# clock.net
KiCad netlist of a schematic drawn in Altium Designer
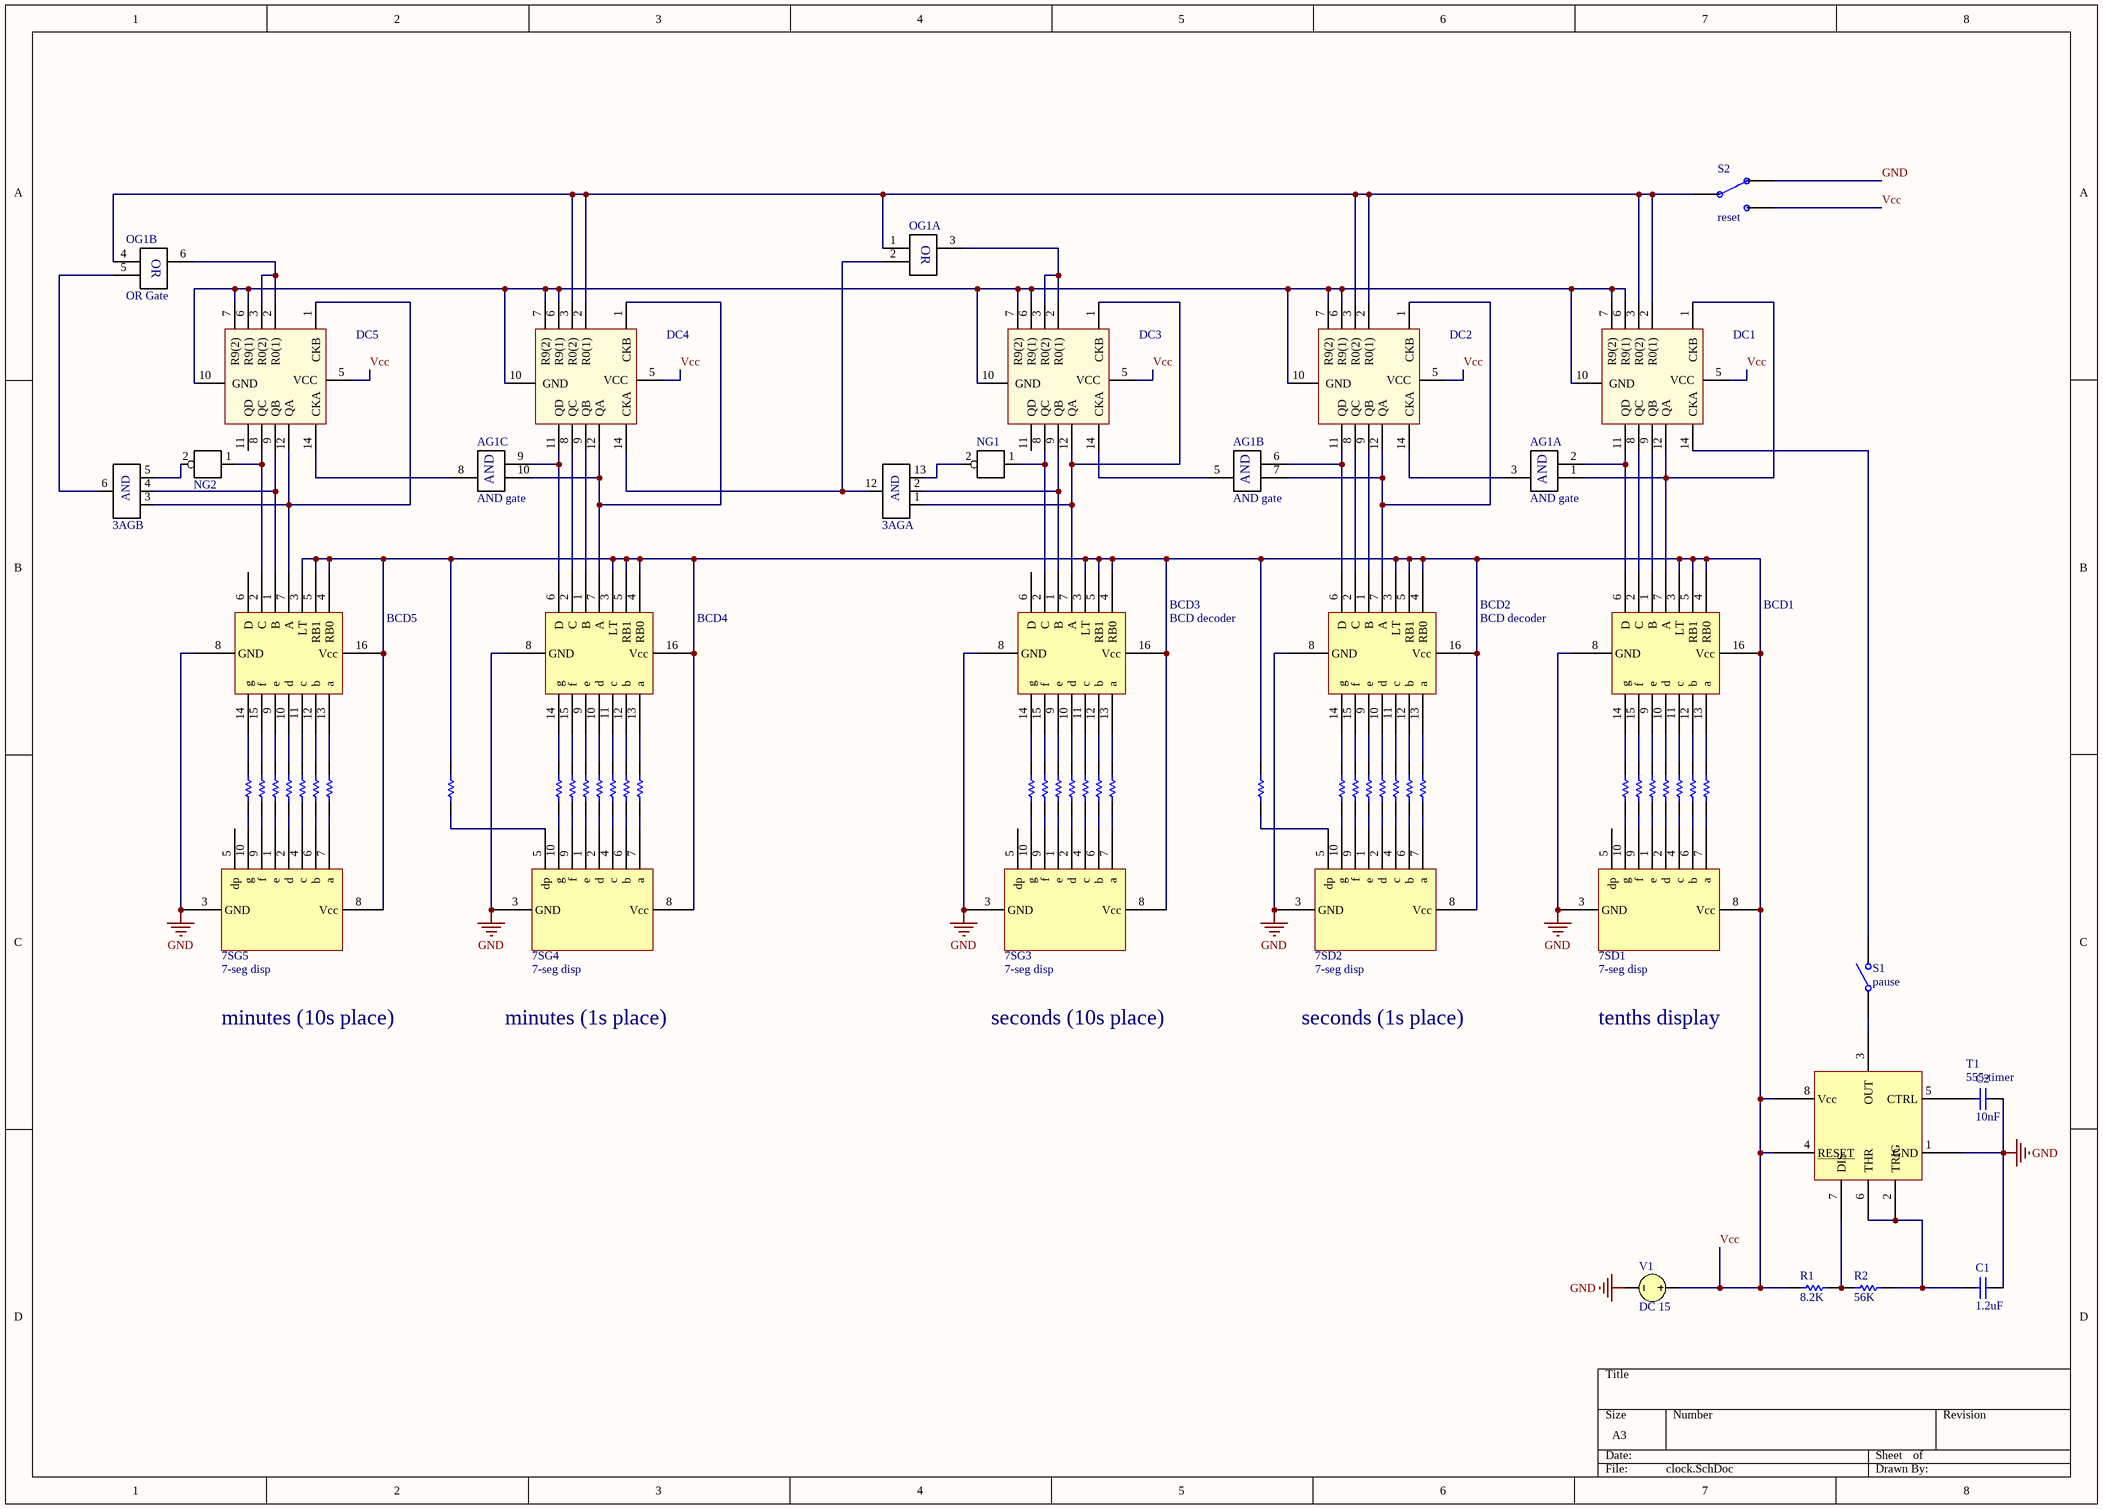
[diagram p0: clock.SchDoc]

(export (version "E")
  (design (tool "Eeschema 10.0.6"))
  (components
    (comp (ref "3AG") (value "DM7411N") (libsource (lib "clockproject") (part "3AND gate")))
    (comp (ref "7SD1") (value "7-seg disp") (libsource (lib "clockproject") (part "7-seg disp")))
    (comp (ref "7SD2") (value "7-seg disp") (libsource (lib "clockproject") (part "7-seg disp")))
    (comp (ref "7SG3") (value "7-seg disp") (libsource (lib "clockproject") (part "7-seg disp")))
    (comp (ref "7SG4") (value "7-seg disp") (libsource (lib "clockproject") (part "7-seg disp")))
    (comp (ref "7SG5") (value "7-seg disp") (libsource (lib "clockproject") (part "7-seg disp")))
    (comp (ref "AG1") (value "AND gate") (libsource (lib "clockproject") (part "AND gate")))
    (comp (ref "BCD1") (value "BCD decoder") (libsource (lib "clockproject") (part "BCD decoder")))
    (comp (ref "BCD2") (value "BCD decoder") (libsource (lib "clockproject") (part "BCD decoder")))
    (comp (ref "BCD3") (value "BCD decoder") (libsource (lib "clockproject") (part "BCD decoder")))
    (comp (ref "BCD4") (value "BCD decoder") (libsource (lib "clockproject") (part "BCD decoder")))
    (comp (ref "BCD5") (value "BCD decoder") (libsource (lib "clockproject") (part "BCD decoder")))
    (comp (ref "C1")
      (value "1.2uF")
      (footprint "RAD-0.3")
      (description "Capacitor")
      (fields (field (name "Comment") "Cap") (field (name "PUBLISHER") "Altium Limited"))
      (libsource (lib "Miscellaneous Devices") (part "Cap"))
    )
    (comp (ref "C2")
      (value "10nF")
      (footprint "RAD-0.3")
      (description "Capacitor")
      (fields (field (name "Comment") "Cap") (field (name "PUBLISHER") "Altium Limited"))
      (libsource (lib "Miscellaneous Devices") (part "Cap"))
    )
    (comp (ref "DC1")
      (value "Decade counter (SN76LS90N)")
      (footprint "SN74LS90N")
      (libsource (lib "clockproject") (part "Decade counter (SN76LS90N)"))
    )
    (comp (ref "DC2")
      (value "Decade counter (SN76LS90N)")
      (footprint "SN74LS90N")
      (libsource (lib "clockproject") (part "Decade counter (SN76LS90N)"))
    )
    (comp (ref "DC3")
      (value "Decade counter (SN76LS90N)")
      (footprint "SN74LS90N")
      (libsource (lib "clockproject") (part "Decade counter (SN76LS90N)"))
    )
    (comp (ref "DC4")
      (value "Decade counter (SN76LS90N)")
      (footprint "SN74LS90N")
      (libsource (lib "clockproject") (part "Decade counter (SN76LS90N)"))
    )
    (comp (ref "DC5")
      (value "Decade counter (SN76LS90N)")
      (footprint "SN74LS90N")
      (libsource (lib "clockproject") (part "Decade counter (SN76LS90N)"))
    )
    (comp (ref "NG1") (value "NOT gate") (libsource (lib "clockproject") (part "NOT gate")))
    (comp (ref "NG2") (value "NOT gate") (libsource (lib "clockproject") (part "NOT gate")))
    (comp (ref "OG1") (value "OR Gate") (libsource (lib "clockproject") (part "OR Gate")))
    (comp (ref "R1")
      (value "8.2K")
      (footprint "AXIAL-0.3")
      (description "Resistor")
      (fields (field (name "Comment") "Res1") (field (name "PUBLISHER") "Altium Limited"))
      (libsource (lib "Miscellaneous Devices") (part "Res1"))
    )
    (comp (ref "R2")
      (value "56K")
      (footprint "AXIAL-0.3")
      (description "Resistor")
      (fields (field (name "Comment") "Res1") (field (name "PUBLISHER") "Altium Limited"))
      (libsource (lib "Miscellaneous Devices") (part "Res1"))
    )
    (comp (ref "R3")
      (value "Res1")
      (footprint "AXIAL-0.3")
      (description "Resistor")
      (fields (field (name "PUBLISHER") "Altium Limited"))
      (libsource (lib "Miscellaneous Devices") (part "Res1"))
    )
    (comp (ref "R4")
      (value "Res1")
      (footprint "AXIAL-0.3")
      (description "Resistor")
      (fields (field (name "PUBLISHER") "Altium Limited"))
      (libsource (lib "Miscellaneous Devices") (part "Res1"))
    )
    (comp (ref "R5")
      (value "Res1")
      (footprint "AXIAL-0.3")
      (description "Resistor")
      (fields (field (name "PUBLISHER") "Altium Limited"))
      (libsource (lib "Miscellaneous Devices") (part "Res1"))
    )
    (comp (ref "R6")
      (value "Res1")
      (footprint "AXIAL-0.3")
      (description "Resistor")
      (fields (field (name "PUBLISHER") "Altium Limited"))
      (libsource (lib "Miscellaneous Devices") (part "Res1"))
    )
    (comp (ref "R7")
      (value "Res1")
      (footprint "AXIAL-0.3")
      (description "Resistor")
      (fields (field (name "PUBLISHER") "Altium Limited"))
      (libsource (lib "Miscellaneous Devices") (part "Res1"))
    )
    (comp (ref "R8")
      (value "Res1")
      (footprint "AXIAL-0.3")
      (description "Resistor")
      (fields (field (name "PUBLISHER") "Altium Limited"))
      (libsource (lib "Miscellaneous Devices") (part "Res1"))
    )
    (comp (ref "R9")
      (value "Res1")
      (footprint "AXIAL-0.3")
      (description "Resistor")
      (fields (field (name "PUBLISHER") "Altium Limited"))
      (libsource (lib "Miscellaneous Devices") (part "Res1"))
    )
    (comp (ref "R10")
      (value "Res1")
      (footprint "AXIAL-0.3")
      (description "Resistor")
      (fields (field (name "PUBLISHER") "Altium Limited"))
      (libsource (lib "Miscellaneous Devices") (part "Res1"))
    )
    (comp (ref "R11")
      (value "Res1")
      (footprint "AXIAL-0.3")
      (description "Resistor")
      (fields (field (name "PUBLISHER") "Altium Limited"))
      (libsource (lib "Miscellaneous Devices") (part "Res1"))
    )
    (comp (ref "R12")
      (value "Res1")
      (footprint "AXIAL-0.3")
      (description "Resistor")
      (fields (field (name "PUBLISHER") "Altium Limited"))
      (libsource (lib "Miscellaneous Devices") (part "Res1"))
    )
    (comp (ref "R13")
      (value "Res1")
      (footprint "AXIAL-0.3")
      (description "Resistor")
      (fields (field (name "PUBLISHER") "Altium Limited"))
      (libsource (lib "Miscellaneous Devices") (part "Res1"))
    )
    (comp (ref "R14")
      (value "Res1")
      (footprint "AXIAL-0.3")
      (description "Resistor")
      (fields (field (name "PUBLISHER") "Altium Limited"))
      (libsource (lib "Miscellaneous Devices") (part "Res1"))
    )
    (comp (ref "R15")
      (value "Res1")
      (footprint "AXIAL-0.3")
      (description "Resistor")
      (fields (field (name "PUBLISHER") "Altium Limited"))
      (libsource (lib "Miscellaneous Devices") (part "Res1"))
    )
    (comp (ref "R16")
      (value "Res1")
      (footprint "AXIAL-0.3")
      (description "Resistor")
      (fields (field (name "PUBLISHER") "Altium Limited"))
      (libsource (lib "Miscellaneous Devices") (part "Res1"))
    )
    (comp (ref "R17")
      (value "Res1")
      (footprint "AXIAL-0.3")
      (description "Resistor")
      (fields (field (name "PUBLISHER") "Altium Limited"))
      (libsource (lib "Miscellaneous Devices") (part "Res1"))
    )
    (comp (ref "R18")
      (value "Res1")
      (footprint "AXIAL-0.3")
      (description "Resistor")
      (fields (field (name "PUBLISHER") "Altium Limited"))
      (libsource (lib "Miscellaneous Devices") (part "Res1"))
    )
    (comp (ref "R19")
      (value "Res1")
      (footprint "AXIAL-0.3")
      (description "Resistor")
      (fields (field (name "PUBLISHER") "Altium Limited"))
      (libsource (lib "Miscellaneous Devices") (part "Res1"))
    )
    (comp (ref "R20")
      (value "Res1")
      (footprint "AXIAL-0.3")
      (description "Resistor")
      (fields (field (name "PUBLISHER") "Altium Limited"))
      (libsource (lib "Miscellaneous Devices") (part "Res1"))
    )
    (comp (ref "R21")
      (value "Res1")
      (footprint "AXIAL-0.3")
      (description "Resistor")
      (fields (field (name "PUBLISHER") "Altium Limited"))
      (libsource (lib "Miscellaneous Devices") (part "Res1"))
    )
    (comp (ref "R22")
      (value "Res1")
      (footprint "AXIAL-0.3")
      (description "Resistor")
      (fields (field (name "PUBLISHER") "Altium Limited"))
      (libsource (lib "Miscellaneous Devices") (part "Res1"))
    )
    (comp (ref "R23")
      (value "Res1")
      (footprint "AXIAL-0.3")
      (description "Resistor")
      (fields (field (name "PUBLISHER") "Altium Limited"))
      (libsource (lib "Miscellaneous Devices") (part "Res1"))
    )
    (comp (ref "R24")
      (value "Res1")
      (footprint "AXIAL-0.3")
      (description "Resistor")
      (fields (field (name "PUBLISHER") "Altium Limited"))
      (libsource (lib "Miscellaneous Devices") (part "Res1"))
    )
    (comp (ref "R25")
      (value "Res1")
      (footprint "AXIAL-0.3")
      (description "Resistor")
      (fields (field (name "PUBLISHER") "Altium Limited"))
      (libsource (lib "Miscellaneous Devices") (part "Res1"))
    )
    (comp (ref "R26")
      (value "Res1")
      (footprint "AXIAL-0.3")
      (description "Resistor")
      (fields (field (name "PUBLISHER") "Altium Limited"))
      (libsource (lib "Miscellaneous Devices") (part "Res1"))
    )
    (comp (ref "R27")
      (value "Res1")
      (footprint "AXIAL-0.3")
      (description "Resistor")
      (fields (field (name "PUBLISHER") "Altium Limited"))
      (libsource (lib "Miscellaneous Devices") (part "Res1"))
    )
    (comp (ref "R28")
      (value "Res1")
      (footprint "AXIAL-0.3")
      (description "Resistor")
      (fields (field (name "PUBLISHER") "Altium Limited"))
      (libsource (lib "Miscellaneous Devices") (part "Res1"))
    )
    (comp (ref "R29")
      (value "Res1")
      (footprint "AXIAL-0.3")
      (description "Resistor")
      (fields (field (name "PUBLISHER") "Altium Limited"))
      (libsource (lib "Miscellaneous Devices") (part "Res1"))
    )
    (comp (ref "R30")
      (value "Res1")
      (footprint "AXIAL-0.3")
      (description "Resistor")
      (fields (field (name "PUBLISHER") "Altium Limited"))
      (libsource (lib "Miscellaneous Devices") (part "Res1"))
    )
    (comp (ref "R31")
      (value "Res1")
      (footprint "AXIAL-0.3")
      (description "Resistor")
      (fields (field (name "PUBLISHER") "Altium Limited"))
      (libsource (lib "Miscellaneous Devices") (part "Res1"))
    )
    (comp (ref "R32")
      (value "Res1")
      (footprint "AXIAL-0.3")
      (description "Resistor")
      (fields (field (name "PUBLISHER") "Altium Limited"))
      (libsource (lib "Miscellaneous Devices") (part "Res1"))
    )
    (comp (ref "R33")
      (value "Res1")
      (footprint "AXIAL-0.3")
      (description "Resistor")
      (fields (field (name "PUBLISHER") "Altium Limited"))
      (libsource (lib "Miscellaneous Devices") (part "Res1"))
    )
    (comp (ref "R34")
      (value "Res1")
      (footprint "AXIAL-0.3")
      (description "Resistor")
      (fields (field (name "PUBLISHER") "Altium Limited"))
      (libsource (lib "Miscellaneous Devices") (part "Res1"))
    )
    (comp (ref "R35")
      (value "Res1")
      (footprint "AXIAL-0.3")
      (description "Resistor")
      (fields (field (name "PUBLISHER") "Altium Limited"))
      (libsource (lib "Miscellaneous Devices") (part "Res1"))
    )
    (comp (ref "R36")
      (value "Res1")
      (footprint "AXIAL-0.3")
      (description "Resistor")
      (fields (field (name "PUBLISHER") "Altium Limited"))
      (libsource (lib "Miscellaneous Devices") (part "Res1"))
    )
    (comp (ref "R37")
      (value "Res1")
      (footprint "AXIAL-0.3")
      (description "Resistor")
      (fields (field (name "PUBLISHER") "Altium Limited"))
      (libsource (lib "Miscellaneous Devices") (part "Res1"))
    )
    (comp (ref "R38")
      (value "Res1")
      (footprint "AXIAL-0.3")
      (description "Resistor")
      (fields (field (name "PUBLISHER") "Altium Limited"))
      (libsource (lib "Miscellaneous Devices") (part "Res1"))
    )
    (comp (ref "R39")
      (value "Res1")
      (footprint "AXIAL-0.3")
      (description "Resistor")
      (fields (field (name "PUBLISHER") "Altium Limited"))
      (libsource (lib "Miscellaneous Devices") (part "Res1"))
    )
    (comp (ref "S1")
      (value "pause")
      (footprint "SPST-2")
      (description "Single-Pole, Single-Throw Switch")
      (fields (field (name "PUBLISHER") "Altium Limited"))
      (libsource (lib "Miscellaneous Devices") (part "SW-SPST"))
    )
    (comp (ref "S2") (value "reset") (footprint "Switch") (libsource (lib "clockproject") (part "Switch")))
    (comp (ref "T1") (value "555-timer") (libsource (lib "clockproject") (part "555-timer")))
    (comp (ref "V1")
      (value "DC 15")
      (description "Voltage Source")
      (fields (field (name "PUBLISHER") "Altium Limited"))
      (libsource (lib "Simulation Generic Components") (part "VSRC"))
    )
  )
  (nets
    (net (code "1") (name "/Vcc") (class "Default")
      (node (ref "7SD1") (pin "8") (pinfunction "Vcc_8") (pintype "passive"))
      (node (ref "7SD2") (pin "8") (pinfunction "Vcc_8") (pintype "passive"))
      (node (ref "7SG3") (pin "8") (pinfunction "Vcc_8") (pintype "passive"))
      (node (ref "7SG4") (pin "8") (pinfunction "Vcc_8") (pintype "passive"))
      (node (ref "7SG5") (pin "8") (pinfunction "Vcc_8") (pintype "passive"))
      (node (ref "BCD1") (pin "16") (pinfunction "Vcc_16") (pintype "passive"))
      (node (ref "BCD1") (pin "3") (pinfunction "LT_3") (pintype "passive"))
      (node (ref "BCD1") (pin "4") (pinfunction "RB0_4") (pintype "passive"))
      (node (ref "BCD1") (pin "5") (pinfunction "RB1_5") (pintype "passive"))
      (node (ref "BCD2") (pin "16") (pinfunction "Vcc_16") (pintype "passive"))
      (node (ref "BCD2") (pin "3") (pinfunction "LT_3") (pintype "passive"))
      (node (ref "BCD2") (pin "4") (pinfunction "RB0_4") (pintype "passive"))
      (node (ref "BCD2") (pin "5") (pinfunction "RB1_5") (pintype "passive"))
      (node (ref "BCD3") (pin "16") (pinfunction "Vcc_16") (pintype "passive"))
      (node (ref "BCD3") (pin "3") (pinfunction "LT_3") (pintype "passive"))
      (node (ref "BCD3") (pin "4") (pinfunction "RB0_4") (pintype "passive"))
      (node (ref "BCD3") (pin "5") (pinfunction "RB1_5") (pintype "passive"))
      (node (ref "BCD4") (pin "16") (pinfunction "Vcc_16") (pintype "passive"))
      (node (ref "BCD4") (pin "3") (pinfunction "LT_3") (pintype "passive"))
      (node (ref "BCD4") (pin "4") (pinfunction "RB0_4") (pintype "passive"))
      (node (ref "BCD4") (pin "5") (pinfunction "RB1_5") (pintype "passive"))
      (node (ref "BCD5") (pin "16") (pinfunction "Vcc_16") (pintype "passive"))
      (node (ref "BCD5") (pin "3") (pinfunction "LT_3") (pintype "passive"))
      (node (ref "BCD5") (pin "4") (pinfunction "RB0_4") (pintype "passive"))
      (node (ref "BCD5") (pin "5") (pinfunction "RB1_5") (pintype "passive"))
      (node (ref "DC1") (pin "5") (pinfunction "VCC_5") (pintype "passive"))
      (node (ref "DC2") (pin "5") (pinfunction "VCC_5") (pintype "passive"))
      (node (ref "DC3") (pin "5") (pinfunction "VCC_5") (pintype "passive"))
      (node (ref "DC4") (pin "5") (pinfunction "VCC_5") (pintype "passive"))
      (node (ref "DC5") (pin "5") (pinfunction "VCC_5") (pintype "passive"))
      (node (ref "R1") (pin "2") (pinfunction "2_2") (pintype "passive"))
      (node (ref "R17") (pin "1") (pinfunction "1_1") (pintype "passive"))
      (node (ref "R32") (pin "1") (pinfunction "1_1") (pintype "passive"))
      (node (ref "S2") (pin "1") (pinfunction "1_1") (pintype "passive"))
      (node (ref "T1") (pin "4") (pinfunction "RESET_4") (pintype "passive"))
      (node (ref "T1") (pin "8") (pinfunction "Vcc_8") (pintype "passive"))
      (node (ref "V1") (pin "1") (pinfunction "1_1") (pintype "passive"))
    )
    (net (code "2") (name "GND") (class "Default")
      (node (ref "7SD1") (pin "3") (pinfunction "GND_3") (pintype "passive"))
      (node (ref "7SD2") (pin "3") (pinfunction "GND_3") (pintype "passive"))
      (node (ref "7SG3") (pin "3") (pinfunction "GND_3") (pintype "passive"))
      (node (ref "7SG4") (pin "3") (pinfunction "GND_3") (pintype "passive"))
      (node (ref "7SG5") (pin "3") (pinfunction "GND_3") (pintype "passive"))
      (node (ref "BCD1") (pin "8") (pinfunction "GND_8") (pintype "passive"))
      (node (ref "BCD2") (pin "8") (pinfunction "GND_8") (pintype "passive"))
      (node (ref "BCD3") (pin "8") (pinfunction "GND_8") (pintype "passive"))
      (node (ref "BCD4") (pin "8") (pinfunction "GND_8") (pintype "passive"))
      (node (ref "BCD5") (pin "8") (pinfunction "GND_8") (pintype "passive"))
      (node (ref "C1") (pin "1") (pinfunction "1_1") (pintype "passive"))
      (node (ref "C2") (pin "1") (pinfunction "1_1") (pintype "passive"))
      (node (ref "S2") (pin "3") (pinfunction "3_3") (pintype "passive"))
      (node (ref "T1") (pin "1") (pinfunction "GND_1") (pintype "passive"))
      (node (ref "V1") (pin "2") (pinfunction "2_2") (pintype "passive"))
    )
    (net (code "3") (name "Net-(3AG-Pad5)") (class "Default")
      (node (ref "3AG") (pin "5") (pinfunction "5_5") (pintype "passive"))
      (node (ref "NG2") (pin "2") (pinfunction "2_2") (pintype "passive"))
    )
    (net (code "4") (name "Net-(3AG-Pad6)") (class "Default")
      (node (ref "3AG") (pin "6") (pinfunction "6_6") (pintype "passive"))
      (node (ref "OG1") (pin "5") (pinfunction "5_5") (pintype "passive"))
    )
    (net (code "5") (name "Net-(3AG-Pad13)") (class "Default")
      (node (ref "3AG") (pin "13") (pinfunction "13_13") (pintype "passive"))
      (node (ref "NG1") (pin "2") (pinfunction "2_2") (pintype "passive"))
    )
    (net (code "6") (name "Net-(7SD1-a)") (class "Default")
      (node (ref "7SD1") (pin "7") (pinfunction "a_7") (pintype "passive"))
      (node (ref "R3") (pin "2") (pinfunction "2_2") (pintype "passive"))
    )
    (net (code "7") (name "Net-(7SD1-b)") (class "Default")
      (node (ref "7SD1") (pin "6") (pinfunction "b_6") (pintype "passive"))
      (node (ref "R4") (pin "2") (pinfunction "2_2") (pintype "passive"))
    )
    (net (code "8") (name "Net-(7SD1-c)") (class "Default")
      (node (ref "7SD1") (pin "4") (pinfunction "c_4") (pintype "passive"))
      (node (ref "R5") (pin "2") (pinfunction "2_2") (pintype "passive"))
    )
    (net (code "9") (name "Net-(7SD1-d)") (class "Default")
      (node (ref "7SD1") (pin "2") (pinfunction "d_2") (pintype "passive"))
      (node (ref "R6") (pin "2") (pinfunction "2_2") (pintype "passive"))
    )
    (net (code "10") (name "Net-(7SD1-e)") (class "Default")
      (node (ref "7SD1") (pin "1") (pinfunction "e_1") (pintype "passive"))
      (node (ref "R7") (pin "2") (pinfunction "2_2") (pintype "passive"))
    )
    (net (code "11") (name "Net-(7SD1-f)") (class "Default")
      (node (ref "7SD1") (pin "9") (pinfunction "f_9") (pintype "passive"))
      (node (ref "R8") (pin "2") (pinfunction "2_2") (pintype "passive"))
    )
    (net (code "12") (name "Net-(7SD1-g)") (class "Default")
      (node (ref "7SD1") (pin "10") (pinfunction "g_10") (pintype "passive"))
      (node (ref "R9") (pin "2") (pinfunction "2_2") (pintype "passive"))
    )
    (net (code "13") (name "Net-(7SD2-a)") (class "Default")
      (node (ref "7SD2") (pin "7") (pinfunction "a_7") (pintype "passive"))
      (node (ref "R10") (pin "2") (pinfunction "2_2") (pintype "passive"))
    )
    (net (code "14") (name "Net-(7SD2-b)") (class "Default")
      (node (ref "7SD2") (pin "6") (pinfunction "b_6") (pintype "passive"))
      (node (ref "R11") (pin "2") (pinfunction "2_2") (pintype "passive"))
    )
    (net (code "15") (name "Net-(7SD2-c)") (class "Default")
      (node (ref "7SD2") (pin "4") (pinfunction "c_4") (pintype "passive"))
      (node (ref "R12") (pin "2") (pinfunction "2_2") (pintype "passive"))
    )
    (net (code "16") (name "Net-(7SD2-d)") (class "Default")
      (node (ref "7SD2") (pin "2") (pinfunction "d_2") (pintype "passive"))
      (node (ref "R13") (pin "2") (pinfunction "2_2") (pintype "passive"))
    )
    (net (code "17") (name "Net-(7SD2-dp)") (class "Default")
      (node (ref "7SD2") (pin "5") (pinfunction "dp_5") (pintype "passive"))
      (node (ref "R17") (pin "2") (pinfunction "2_2") (pintype "passive"))
    )
    (net (code "18") (name "Net-(7SD2-e)") (class "Default")
      (node (ref "7SD2") (pin "1") (pinfunction "e_1") (pintype "passive"))
      (node (ref "R14") (pin "2") (pinfunction "2_2") (pintype "passive"))
    )
    (net (code "19") (name "Net-(7SD2-f)") (class "Default")
      (node (ref "7SD2") (pin "9") (pinfunction "f_9") (pintype "passive"))
      (node (ref "R15") (pin "2") (pinfunction "2_2") (pintype "passive"))
    )
    (net (code "20") (name "Net-(7SD2-g)") (class "Default")
      (node (ref "7SD2") (pin "10") (pinfunction "g_10") (pintype "passive"))
      (node (ref "R16") (pin "2") (pinfunction "2_2") (pintype "passive"))
    )
    (net (code "21") (name "Net-(7SG3-a)") (class "Default")
      (node (ref "7SG3") (pin "7") (pinfunction "a_7") (pintype "passive"))
      (node (ref "R18") (pin "2") (pinfunction "2_2") (pintype "passive"))
    )
    (net (code "22") (name "Net-(7SG3-b)") (class "Default")
      (node (ref "7SG3") (pin "6") (pinfunction "b_6") (pintype "passive"))
      (node (ref "R19") (pin "2") (pinfunction "2_2") (pintype "passive"))
    )
    (net (code "23") (name "Net-(7SG3-c)") (class "Default")
      (node (ref "7SG3") (pin "4") (pinfunction "c_4") (pintype "passive"))
      (node (ref "R20") (pin "2") (pinfunction "2_2") (pintype "passive"))
    )
    (net (code "24") (name "Net-(7SG3-d)") (class "Default")
      (node (ref "7SG3") (pin "2") (pinfunction "d_2") (pintype "passive"))
      (node (ref "R21") (pin "2") (pinfunction "2_2") (pintype "passive"))
    )
    (net (code "25") (name "Net-(7SG3-e)") (class "Default")
      (node (ref "7SG3") (pin "1") (pinfunction "e_1") (pintype "passive"))
      (node (ref "R22") (pin "2") (pinfunction "2_2") (pintype "passive"))
    )
    (net (code "26") (name "Net-(7SG3-f)") (class "Default")
      (node (ref "7SG3") (pin "9") (pinfunction "f_9") (pintype "passive"))
      (node (ref "R23") (pin "2") (pinfunction "2_2") (pintype "passive"))
    )
    (net (code "27") (name "Net-(7SG3-g)") (class "Default")
      (node (ref "7SG3") (pin "10") (pinfunction "g_10") (pintype "passive"))
      (node (ref "R24") (pin "2") (pinfunction "2_2") (pintype "passive"))
    )
    (net (code "28") (name "Net-(7SG4-a)") (class "Default")
      (node (ref "7SG4") (pin "7") (pinfunction "a_7") (pintype "passive"))
      (node (ref "R25") (pin "2") (pinfunction "2_2") (pintype "passive"))
    )
    (net (code "29") (name "Net-(7SG4-b)") (class "Default")
      (node (ref "7SG4") (pin "6") (pinfunction "b_6") (pintype "passive"))
      (node (ref "R26") (pin "2") (pinfunction "2_2") (pintype "passive"))
    )
    (net (code "30") (name "Net-(7SG4-c)") (class "Default")
      (node (ref "7SG4") (pin "4") (pinfunction "c_4") (pintype "passive"))
      (node (ref "R27") (pin "2") (pinfunction "2_2") (pintype "passive"))
    )
    (net (code "31") (name "Net-(7SG4-d)") (class "Default")
      (node (ref "7SG4") (pin "2") (pinfunction "d_2") (pintype "passive"))
      (node (ref "R28") (pin "2") (pinfunction "2_2") (pintype "passive"))
    )
    (net (code "32") (name "Net-(7SG4-dp)") (class "Default")
      (node (ref "7SG4") (pin "5") (pinfunction "dp_5") (pintype "passive"))
      (node (ref "R32") (pin "2") (pinfunction "2_2") (pintype "passive"))
    )
    (net (code "33") (name "Net-(7SG4-e)") (class "Default")
      (node (ref "7SG4") (pin "1") (pinfunction "e_1") (pintype "passive"))
      (node (ref "R29") (pin "2") (pinfunction "2_2") (pintype "passive"))
    )
    (net (code "34") (name "Net-(7SG4-f)") (class "Default")
      (node (ref "7SG4") (pin "9") (pinfunction "f_9") (pintype "passive"))
      (node (ref "R30") (pin "2") (pinfunction "2_2") (pintype "passive"))
    )
    (net (code "35") (name "Net-(7SG4-g)") (class "Default")
      (node (ref "7SG4") (pin "10") (pinfunction "g_10") (pintype "passive"))
      (node (ref "R31") (pin "2") (pinfunction "2_2") (pintype "passive"))
    )
    (net (code "36") (name "Net-(7SG5-a)") (class "Default")
      (node (ref "7SG5") (pin "7") (pinfunction "a_7") (pintype "passive"))
      (node (ref "R33") (pin "2") (pinfunction "2_2") (pintype "passive"))
    )
    (net (code "37") (name "Net-(7SG5-b)") (class "Default")
      (node (ref "7SG5") (pin "6") (pinfunction "b_6") (pintype "passive"))
      (node (ref "R34") (pin "2") (pinfunction "2_2") (pintype "passive"))
    )
    (net (code "38") (name "Net-(7SG5-c)") (class "Default")
      (node (ref "7SG5") (pin "4") (pinfunction "c_4") (pintype "passive"))
      (node (ref "R35") (pin "2") (pinfunction "2_2") (pintype "passive"))
    )
    (net (code "39") (name "Net-(7SG5-d)") (class "Default")
      (node (ref "7SG5") (pin "2") (pinfunction "d_2") (pintype "passive"))
      (node (ref "R36") (pin "2") (pinfunction "2_2") (pintype "passive"))
    )
    (net (code "40") (name "Net-(7SG5-e)") (class "Default")
      (node (ref "7SG5") (pin "1") (pinfunction "e_1") (pintype "passive"))
      (node (ref "R37") (pin "2") (pinfunction "2_2") (pintype "passive"))
    )
    (net (code "41") (name "Net-(7SG5-f)") (class "Default")
      (node (ref "7SG5") (pin "9") (pinfunction "f_9") (pintype "passive"))
      (node (ref "R38") (pin "2") (pinfunction "2_2") (pintype "passive"))
    )
    (net (code "42") (name "Net-(7SG5-g)") (class "Default")
      (node (ref "7SG5") (pin "10") (pinfunction "g_10") (pintype "passive"))
      (node (ref "R39") (pin "2") (pinfunction "2_2") (pintype "passive"))
    )
    (net (code "43") (name "Net-(BCD1-A)") (class "Default")
      (node (ref "AG1") (pin "1") (pinfunction "1_1") (pintype "passive"))
      (node (ref "BCD1") (pin "7") (pinfunction "A_7") (pintype "passive"))
      (node (ref "DC1") (pin "1") (pinfunction "CKB_1") (pintype "passive"))
      (node (ref "DC1") (pin "12") (pinfunction "QA_12") (pintype "passive"))
    )
    (net (code "44") (name "Net-(BCD1-B)") (class "Default")
      (node (ref "BCD1") (pin "1") (pinfunction "B_1") (pintype "passive"))
      (node (ref "DC1") (pin "9") (pinfunction "QB_9") (pintype "passive"))
    )
    (net (code "45") (name "Net-(BCD1-C)") (class "Default")
      (node (ref "BCD1") (pin "2") (pinfunction "C_2") (pintype "passive"))
      (node (ref "DC1") (pin "8") (pinfunction "QC_8") (pintype "passive"))
    )
    (net (code "46") (name "Net-(BCD1-D)") (class "Default")
      (node (ref "AG1") (pin "2") (pinfunction "2_2") (pintype "passive"))
      (node (ref "BCD1") (pin "6") (pinfunction "D_6") (pintype "passive"))
      (node (ref "DC1") (pin "11") (pinfunction "QD_11") (pintype "passive"))
    )
    (net (code "47") (name "Net-(BCD1-a)") (class "Default")
      (node (ref "BCD1") (pin "13") (pinfunction "a_13") (pintype "passive"))
      (node (ref "R3") (pin "1") (pinfunction "1_1") (pintype "passive"))
    )
    (net (code "48") (name "Net-(BCD1-b)") (class "Default")
      (node (ref "BCD1") (pin "12") (pinfunction "b_12") (pintype "passive"))
      (node (ref "R4") (pin "1") (pinfunction "1_1") (pintype "passive"))
    )
    (net (code "49") (name "Net-(BCD1-c)") (class "Default")
      (node (ref "BCD1") (pin "11") (pinfunction "c_11") (pintype "passive"))
      (node (ref "R5") (pin "1") (pinfunction "1_1") (pintype "passive"))
    )
    (net (code "50") (name "Net-(BCD1-d)") (class "Default")
      (node (ref "BCD1") (pin "10") (pinfunction "d_10") (pintype "passive"))
      (node (ref "R6") (pin "1") (pinfunction "1_1") (pintype "passive"))
    )
    (net (code "51") (name "Net-(BCD1-e)") (class "Default")
      (node (ref "BCD1") (pin "9") (pinfunction "e_9") (pintype "passive"))
      (node (ref "R7") (pin "1") (pinfunction "1_1") (pintype "passive"))
    )
    (net (code "52") (name "Net-(BCD1-f)") (class "Default")
      (node (ref "BCD1") (pin "15") (pinfunction "f_15") (pintype "passive"))
      (node (ref "R8") (pin "1") (pinfunction "1_1") (pintype "passive"))
    )
    (net (code "53") (name "Net-(BCD1-g)") (class "Default")
      (node (ref "BCD1") (pin "14") (pinfunction "g_14") (pintype "passive"))
      (node (ref "R9") (pin "1") (pinfunction "1_1") (pintype "passive"))
    )
    (net (code "54") (name "Net-(BCD2-A)") (class "Default")
      (node (ref "AG1") (pin "7") (pinfunction "7_7") (pintype "passive"))
      (node (ref "BCD2") (pin "7") (pinfunction "A_7") (pintype "passive"))
      (node (ref "DC2") (pin "1") (pinfunction "CKB_1") (pintype "passive"))
      (node (ref "DC2") (pin "12") (pinfunction "QA_12") (pintype "passive"))
    )
    (net (code "55") (name "Net-(BCD2-B)") (class "Default")
      (node (ref "BCD2") (pin "1") (pinfunction "B_1") (pintype "passive"))
      (node (ref "DC2") (pin "9") (pinfunction "QB_9") (pintype "passive"))
    )
    (net (code "56") (name "Net-(BCD2-C)") (class "Default")
      (node (ref "BCD2") (pin "2") (pinfunction "C_2") (pintype "passive"))
      (node (ref "DC2") (pin "8") (pinfunction "QC_8") (pintype "passive"))
    )
    (net (code "57") (name "Net-(BCD2-D)") (class "Default")
      (node (ref "AG1") (pin "6") (pinfunction "6_6") (pintype "passive"))
      (node (ref "BCD2") (pin "6") (pinfunction "D_6") (pintype "passive"))
      (node (ref "DC2") (pin "11") (pinfunction "QD_11") (pintype "passive"))
    )
    (net (code "58") (name "Net-(BCD2-a)") (class "Default")
      (node (ref "BCD2") (pin "13") (pinfunction "a_13") (pintype "passive"))
      (node (ref "R10") (pin "1") (pinfunction "1_1") (pintype "passive"))
    )
    (net (code "59") (name "Net-(BCD2-b)") (class "Default")
      (node (ref "BCD2") (pin "12") (pinfunction "b_12") (pintype "passive"))
      (node (ref "R11") (pin "1") (pinfunction "1_1") (pintype "passive"))
    )
    (net (code "60") (name "Net-(BCD2-c)") (class "Default")
      (node (ref "BCD2") (pin "11") (pinfunction "c_11") (pintype "passive"))
      (node (ref "R12") (pin "1") (pinfunction "1_1") (pintype "passive"))
    )
    (net (code "61") (name "Net-(BCD2-d)") (class "Default")
      (node (ref "BCD2") (pin "10") (pinfunction "d_10") (pintype "passive"))
      (node (ref "R13") (pin "1") (pinfunction "1_1") (pintype "passive"))
    )
    (net (code "62") (name "Net-(BCD2-e)") (class "Default")
      (node (ref "BCD2") (pin "9") (pinfunction "e_9") (pintype "passive"))
      (node (ref "R14") (pin "1") (pinfunction "1_1") (pintype "passive"))
    )
    (net (code "63") (name "Net-(BCD2-f)") (class "Default")
      (node (ref "BCD2") (pin "15") (pinfunction "f_15") (pintype "passive"))
      (node (ref "R15") (pin "1") (pinfunction "1_1") (pintype "passive"))
    )
    (net (code "64") (name "Net-(BCD2-g)") (class "Default")
      (node (ref "BCD2") (pin "14") (pinfunction "g_14") (pintype "passive"))
      (node (ref "R16") (pin "1") (pinfunction "1_1") (pintype "passive"))
    )
    (net (code "65") (name "Net-(BCD3-A)") (class "Default")
      (node (ref "3AG") (pin "1") (pinfunction "1_1") (pintype "passive"))
      (node (ref "BCD3") (pin "7") (pinfunction "A_7") (pintype "passive"))
      (node (ref "DC3") (pin "1") (pinfunction "CKB_1") (pintype "passive"))
      (node (ref "DC3") (pin "12") (pinfunction "QA_12") (pintype "passive"))
    )
    (net (code "66") (name "Net-(BCD3-B)") (class "Default")
      (node (ref "3AG") (pin "2") (pinfunction "2_2") (pintype "passive"))
      (node (ref "BCD3") (pin "1") (pinfunction "B_1") (pintype "passive"))
      (node (ref "DC3") (pin "9") (pinfunction "QB_9") (pintype "passive"))
    )
    (net (code "67") (name "Net-(BCD3-C)") (class "Default")
      (node (ref "BCD3") (pin "2") (pinfunction "C_2") (pintype "passive"))
      (node (ref "DC3") (pin "8") (pinfunction "QC_8") (pintype "passive"))
      (node (ref "NG1") (pin "1") (pinfunction "1_1") (pintype "passive"))
    )
    (net (code "68") (name "Net-(BCD3-a)") (class "Default")
      (node (ref "BCD3") (pin "13") (pinfunction "a_13") (pintype "passive"))
      (node (ref "R18") (pin "1") (pinfunction "1_1") (pintype "passive"))
    )
    (net (code "69") (name "Net-(BCD3-b)") (class "Default")
      (node (ref "BCD3") (pin "12") (pinfunction "b_12") (pintype "passive"))
      (node (ref "R19") (pin "1") (pinfunction "1_1") (pintype "passive"))
    )
    (net (code "70") (name "Net-(BCD3-c)") (class "Default")
      (node (ref "BCD3") (pin "11") (pinfunction "c_11") (pintype "passive"))
      (node (ref "R20") (pin "1") (pinfunction "1_1") (pintype "passive"))
    )
    (net (code "71") (name "Net-(BCD3-d)") (class "Default")
      (node (ref "BCD3") (pin "10") (pinfunction "d_10") (pintype "passive"))
      (node (ref "R21") (pin "1") (pinfunction "1_1") (pintype "passive"))
    )
    (net (code "72") (name "Net-(BCD3-e)") (class "Default")
      (node (ref "BCD3") (pin "9") (pinfunction "e_9") (pintype "passive"))
      (node (ref "R22") (pin "1") (pinfunction "1_1") (pintype "passive"))
    )
    (net (code "73") (name "Net-(BCD3-f)") (class "Default")
      (node (ref "BCD3") (pin "15") (pinfunction "f_15") (pintype "passive"))
      (node (ref "R23") (pin "1") (pinfunction "1_1") (pintype "passive"))
    )
    (net (code "74") (name "Net-(BCD3-g)") (class "Default")
      (node (ref "BCD3") (pin "14") (pinfunction "g_14") (pintype "passive"))
      (node (ref "R24") (pin "1") (pinfunction "1_1") (pintype "passive"))
    )
    (net (code "75") (name "Net-(BCD4-A)") (class "Default")
      (node (ref "AG1") (pin "10") (pinfunction "10_10") (pintype "passive"))
      (node (ref "BCD4") (pin "7") (pinfunction "A_7") (pintype "passive"))
      (node (ref "DC4") (pin "1") (pinfunction "CKB_1") (pintype "passive"))
      (node (ref "DC4") (pin "12") (pinfunction "QA_12") (pintype "passive"))
    )
    (net (code "76") (name "Net-(BCD4-B)") (class "Default")
      (node (ref "BCD4") (pin "1") (pinfunction "B_1") (pintype "passive"))
      (node (ref "DC4") (pin "9") (pinfunction "QB_9") (pintype "passive"))
    )
    (net (code "77") (name "Net-(BCD4-C)") (class "Default")
      (node (ref "BCD4") (pin "2") (pinfunction "C_2") (pintype "passive"))
      (node (ref "DC4") (pin "8") (pinfunction "QC_8") (pintype "passive"))
    )
    (net (code "78") (name "Net-(BCD4-D)") (class "Default")
      (node (ref "AG1") (pin "9") (pinfunction "9_9") (pintype "passive"))
      (node (ref "BCD4") (pin "6") (pinfunction "D_6") (pintype "passive"))
      (node (ref "DC4") (pin "11") (pinfunction "QD_11") (pintype "passive"))
    )
    (net (code "79") (name "Net-(BCD4-a)") (class "Default")
      (node (ref "BCD4") (pin "13") (pinfunction "a_13") (pintype "passive"))
      (node (ref "R25") (pin "1") (pinfunction "1_1") (pintype "passive"))
    )
    (net (code "80") (name "Net-(BCD4-b)") (class "Default")
      (node (ref "BCD4") (pin "12") (pinfunction "b_12") (pintype "passive"))
      (node (ref "R26") (pin "1") (pinfunction "1_1") (pintype "passive"))
    )
    (net (code "81") (name "Net-(BCD4-c)") (class "Default")
      (node (ref "BCD4") (pin "11") (pinfunction "c_11") (pintype "passive"))
      (node (ref "R27") (pin "1") (pinfunction "1_1") (pintype "passive"))
    )
    (net (code "82") (name "Net-(BCD4-d)") (class "Default")
      (node (ref "BCD4") (pin "10") (pinfunction "d_10") (pintype "passive"))
      (node (ref "R28") (pin "1") (pinfunction "1_1") (pintype "passive"))
    )
    (net (code "83") (name "Net-(BCD4-e)") (class "Default")
      (node (ref "BCD4") (pin "9") (pinfunction "e_9") (pintype "passive"))
      (node (ref "R29") (pin "1") (pinfunction "1_1") (pintype "passive"))
    )
    (net (code "84") (name "Net-(BCD4-f)") (class "Default")
      (node (ref "BCD4") (pin "15") (pinfunction "f_15") (pintype "passive"))
      (node (ref "R30") (pin "1") (pinfunction "1_1") (pintype "passive"))
    )
    (net (code "85") (name "Net-(BCD4-g)") (class "Default")
      (node (ref "BCD4") (pin "14") (pinfunction "g_14") (pintype "passive"))
      (node (ref "R31") (pin "1") (pinfunction "1_1") (pintype "passive"))
    )
    (net (code "86") (name "Net-(BCD5-A)") (class "Default")
      (node (ref "3AG") (pin "3") (pinfunction "3_3") (pintype "passive"))
      (node (ref "BCD5") (pin "7") (pinfunction "A_7") (pintype "passive"))
      (node (ref "DC5") (pin "1") (pinfunction "CKB_1") (pintype "passive"))
      (node (ref "DC5") (pin "12") (pinfunction "QA_12") (pintype "passive"))
    )
    (net (code "87") (name "Net-(BCD5-B)") (class "Default")
      (node (ref "3AG") (pin "4") (pinfunction "4_4") (pintype "passive"))
      (node (ref "BCD5") (pin "1") (pinfunction "B_1") (pintype "passive"))
      (node (ref "DC5") (pin "9") (pinfunction "QB_9") (pintype "passive"))
    )
    (net (code "88") (name "Net-(BCD5-C)") (class "Default")
      (node (ref "BCD5") (pin "2") (pinfunction "C_2") (pintype "passive"))
      (node (ref "DC5") (pin "8") (pinfunction "QC_8") (pintype "passive"))
      (node (ref "NG2") (pin "1") (pinfunction "1_1") (pintype "passive"))
    )
    (net (code "89") (name "Net-(BCD5-a)") (class "Default")
      (node (ref "BCD5") (pin "13") (pinfunction "a_13") (pintype "passive"))
      (node (ref "R33") (pin "1") (pinfunction "1_1") (pintype "passive"))
    )
    (net (code "90") (name "Net-(BCD5-b)") (class "Default")
      (node (ref "BCD5") (pin "12") (pinfunction "b_12") (pintype "passive"))
      (node (ref "R34") (pin "1") (pinfunction "1_1") (pintype "passive"))
    )
    (net (code "91") (name "Net-(BCD5-c)") (class "Default")
      (node (ref "BCD5") (pin "11") (pinfunction "c_11") (pintype "passive"))
      (node (ref "R35") (pin "1") (pinfunction "1_1") (pintype "passive"))
    )
    (net (code "92") (name "Net-(BCD5-d)") (class "Default")
      (node (ref "BCD5") (pin "10") (pinfunction "d_10") (pintype "passive"))
      (node (ref "R36") (pin "1") (pinfunction "1_1") (pintype "passive"))
    )
    (net (code "93") (name "Net-(BCD5-e)") (class "Default")
      (node (ref "BCD5") (pin "9") (pinfunction "e_9") (pintype "passive"))
      (node (ref "R37") (pin "1") (pinfunction "1_1") (pintype "passive"))
    )
    (net (code "94") (name "Net-(BCD5-f)") (class "Default")
      (node (ref "BCD5") (pin "15") (pinfunction "f_15") (pintype "passive"))
      (node (ref "R38") (pin "1") (pinfunction "1_1") (pintype "passive"))
    )
    (net (code "95") (name "Net-(BCD5-g)") (class "Default")
      (node (ref "BCD5") (pin "14") (pinfunction "g_14") (pintype "passive"))
      (node (ref "R39") (pin "1") (pinfunction "1_1") (pintype "passive"))
    )
    (net (code "96") (name "Net-(DC1-CKA)") (class "Default")
      (node (ref "DC1") (pin "14") (pinfunction "CKA_14") (pintype "passive"))
      (node (ref "S1") (pin "2") (pinfunction "NO_2") (pintype "passive"))
    )
    (net (code "97") (name "Net-(DC1-GND)") (class "Default")
      (node (ref "DC1") (pin "10") (pinfunction "GND_10") (pintype "passive"))
      (node (ref "DC1") (pin "6") (pinfunction "R9(1)_6") (pintype "passive"))
      (node (ref "DC1") (pin "7") (pinfunction "R9(2)_7") (pintype "passive"))
      (node (ref "DC2") (pin "10") (pinfunction "GND_10") (pintype "passive"))
      (node (ref "DC2") (pin "6") (pinfunction "R9(1)_6") (pintype "passive"))
      (node (ref "DC2") (pin "7") (pinfunction "R9(2)_7") (pintype "passive"))
      (node (ref "DC3") (pin "10") (pinfunction "GND_10") (pintype "passive"))
      (node (ref "DC3") (pin "6") (pinfunction "R9(1)_6") (pintype "passive"))
      (node (ref "DC3") (pin "7") (pinfunction "R9(2)_7") (pintype "passive"))
      (node (ref "DC4") (pin "10") (pinfunction "GND_10") (pintype "passive"))
      (node (ref "DC4") (pin "6") (pinfunction "R9(1)_6") (pintype "passive"))
      (node (ref "DC4") (pin "7") (pinfunction "R9(2)_7") (pintype "passive"))
      (node (ref "DC5") (pin "10") (pinfunction "GND_10") (pintype "passive"))
      (node (ref "DC5") (pin "6") (pinfunction "R9(1)_6") (pintype "passive"))
      (node (ref "DC5") (pin "7") (pinfunction "R9(2)_7") (pintype "passive"))
    )
    (net (code "98") (name "Net-(DC1-R0(1))") (class "Default")
      (node (ref "DC1") (pin "2") (pinfunction "R0(1)_2") (pintype "passive"))
      (node (ref "DC1") (pin "3") (pinfunction "R0(2)_3") (pintype "passive"))
      (node (ref "DC2") (pin "2") (pinfunction "R0(1)_2") (pintype "passive"))
      (node (ref "DC2") (pin "3") (pinfunction "R0(2)_3") (pintype "passive"))
      (node (ref "DC4") (pin "2") (pinfunction "R0(1)_2") (pintype "passive"))
      (node (ref "DC4") (pin "3") (pinfunction "R0(2)_3") (pintype "passive"))
      (node (ref "OG1") (pin "1") (pinfunction "1_1") (pintype "passive"))
      (node (ref "OG1") (pin "4") (pinfunction "4_4") (pintype "passive"))
      (node (ref "S2") (pin "2") (pinfunction "2_2") (pintype "passive"))
    )
    (net (code "99") (name "Net-(DC2-CKA)") (class "Default")
      (node (ref "AG1") (pin "3") (pinfunction "3_3") (pintype "passive"))
      (node (ref "DC2") (pin "14") (pinfunction "CKA_14") (pintype "passive"))
    )
    (net (code "100") (name "Net-(DC3-CKA)") (class "Default")
      (node (ref "AG1") (pin "5") (pinfunction "5_5") (pintype "passive"))
      (node (ref "DC3") (pin "14") (pinfunction "CKA_14") (pintype "passive"))
    )
    (net (code "101") (name "Net-(DC3-R0(1))") (class "Default")
      (node (ref "DC3") (pin "2") (pinfunction "R0(1)_2") (pintype "passive"))
      (node (ref "DC3") (pin "3") (pinfunction "R0(2)_3") (pintype "passive"))
      (node (ref "OG1") (pin "3") (pinfunction "3_3") (pintype "passive"))
    )
    (net (code "102") (name "Net-(DC4-CKA)") (class "Default")
      (node (ref "3AG") (pin "12") (pinfunction "12_12") (pintype "passive"))
      (node (ref "DC4") (pin "14") (pinfunction "CKA_14") (pintype "passive"))
      (node (ref "OG1") (pin "2") (pinfunction "2_2") (pintype "passive"))
    )
    (net (code "103") (name "Net-(DC5-CKA)") (class "Default")
      (node (ref "AG1") (pin "8") (pinfunction "8_8") (pintype "passive"))
      (node (ref "DC5") (pin "14") (pinfunction "CKA_14") (pintype "passive"))
    )
    (net (code "104") (name "Net-(DC5-R0(1))") (class "Default")
      (node (ref "DC5") (pin "2") (pinfunction "R0(1)_2") (pintype "passive"))
      (node (ref "DC5") (pin "3") (pinfunction "R0(2)_3") (pintype "passive"))
      (node (ref "OG1") (pin "6") (pinfunction "6_6") (pintype "passive"))
    )
    (net (code "105") (name "Net-(S1-COMMON)") (class "Default")
      (node (ref "S1") (pin "1") (pinfunction "COMMON_1") (pintype "passive"))
      (node (ref "T1") (pin "3") (pinfunction "OUT_3") (pintype "passive"))
    )
    (net (code "106") (name "Net-(T1-CTRL)") (class "Default")
      (node (ref "C2") (pin "2") (pinfunction "2_2") (pintype "passive"))
      (node (ref "T1") (pin "5") (pinfunction "CTRL_5") (pintype "passive"))
    )
    (net (code "107") (name "Net-(T1-DIS)") (class "Default")
      (node (ref "R1") (pin "1") (pinfunction "1_1") (pintype "passive"))
      (node (ref "R2") (pin "2") (pinfunction "2_2") (pintype "passive"))
      (node (ref "T1") (pin "7") (pinfunction "DIS_7") (pintype "passive"))
    )
    (net (code "108") (name "Net-(T1-THR)") (class "Default")
      (node (ref "C1") (pin "2") (pinfunction "2_2") (pintype "passive"))
      (node (ref "R2") (pin "1") (pinfunction "1_1") (pintype "passive"))
      (node (ref "T1") (pin "2") (pinfunction "TRIG_2") (pintype "passive"))
      (node (ref "T1") (pin "6") (pinfunction "THR_6") (pintype "passive"))
    )
    (net (code "109") (name "unconnected-(7SD1-dp-Pad5)") (class "Default")
      (node (ref "7SD1") (pin "5") (pinfunction "dp_5") (pintype "passive"))
    )
    (net (code "110") (name "unconnected-(7SG3-dp-Pad5)") (class "Default")
      (node (ref "7SG3") (pin "5") (pinfunction "dp_5") (pintype "passive"))
    )
    (net (code "111") (name "unconnected-(7SG5-dp-Pad5)") (class "Default")
      (node (ref "7SG5") (pin "5") (pinfunction "dp_5") (pintype "passive"))
    )
    (net (code "112") (name "unconnected-(BCD3-D-Pad6)") (class "Default")
      (node (ref "BCD3") (pin "6") (pinfunction "D_6") (pintype "passive"))
    )
    (net (code "113") (name "unconnected-(BCD5-D-Pad6)") (class "Default")
      (node (ref "BCD5") (pin "6") (pinfunction "D_6") (pintype "passive"))
    )
    (net (code "114") (name "unconnected-(DC3-QD-Pad11)") (class "Default")
      (node (ref "DC3") (pin "11") (pinfunction "QD_11") (pintype "passive"))
    )
    (net (code "115") (name "unconnected-(DC5-QD-Pad11)") (class "Default")
      (node (ref "DC5") (pin "11") (pinfunction "QD_11") (pintype "passive"))
    )
  )
)
